# Canadian_Maid_v3.net
KiCad netlist of a schematic drawn in EAGLE
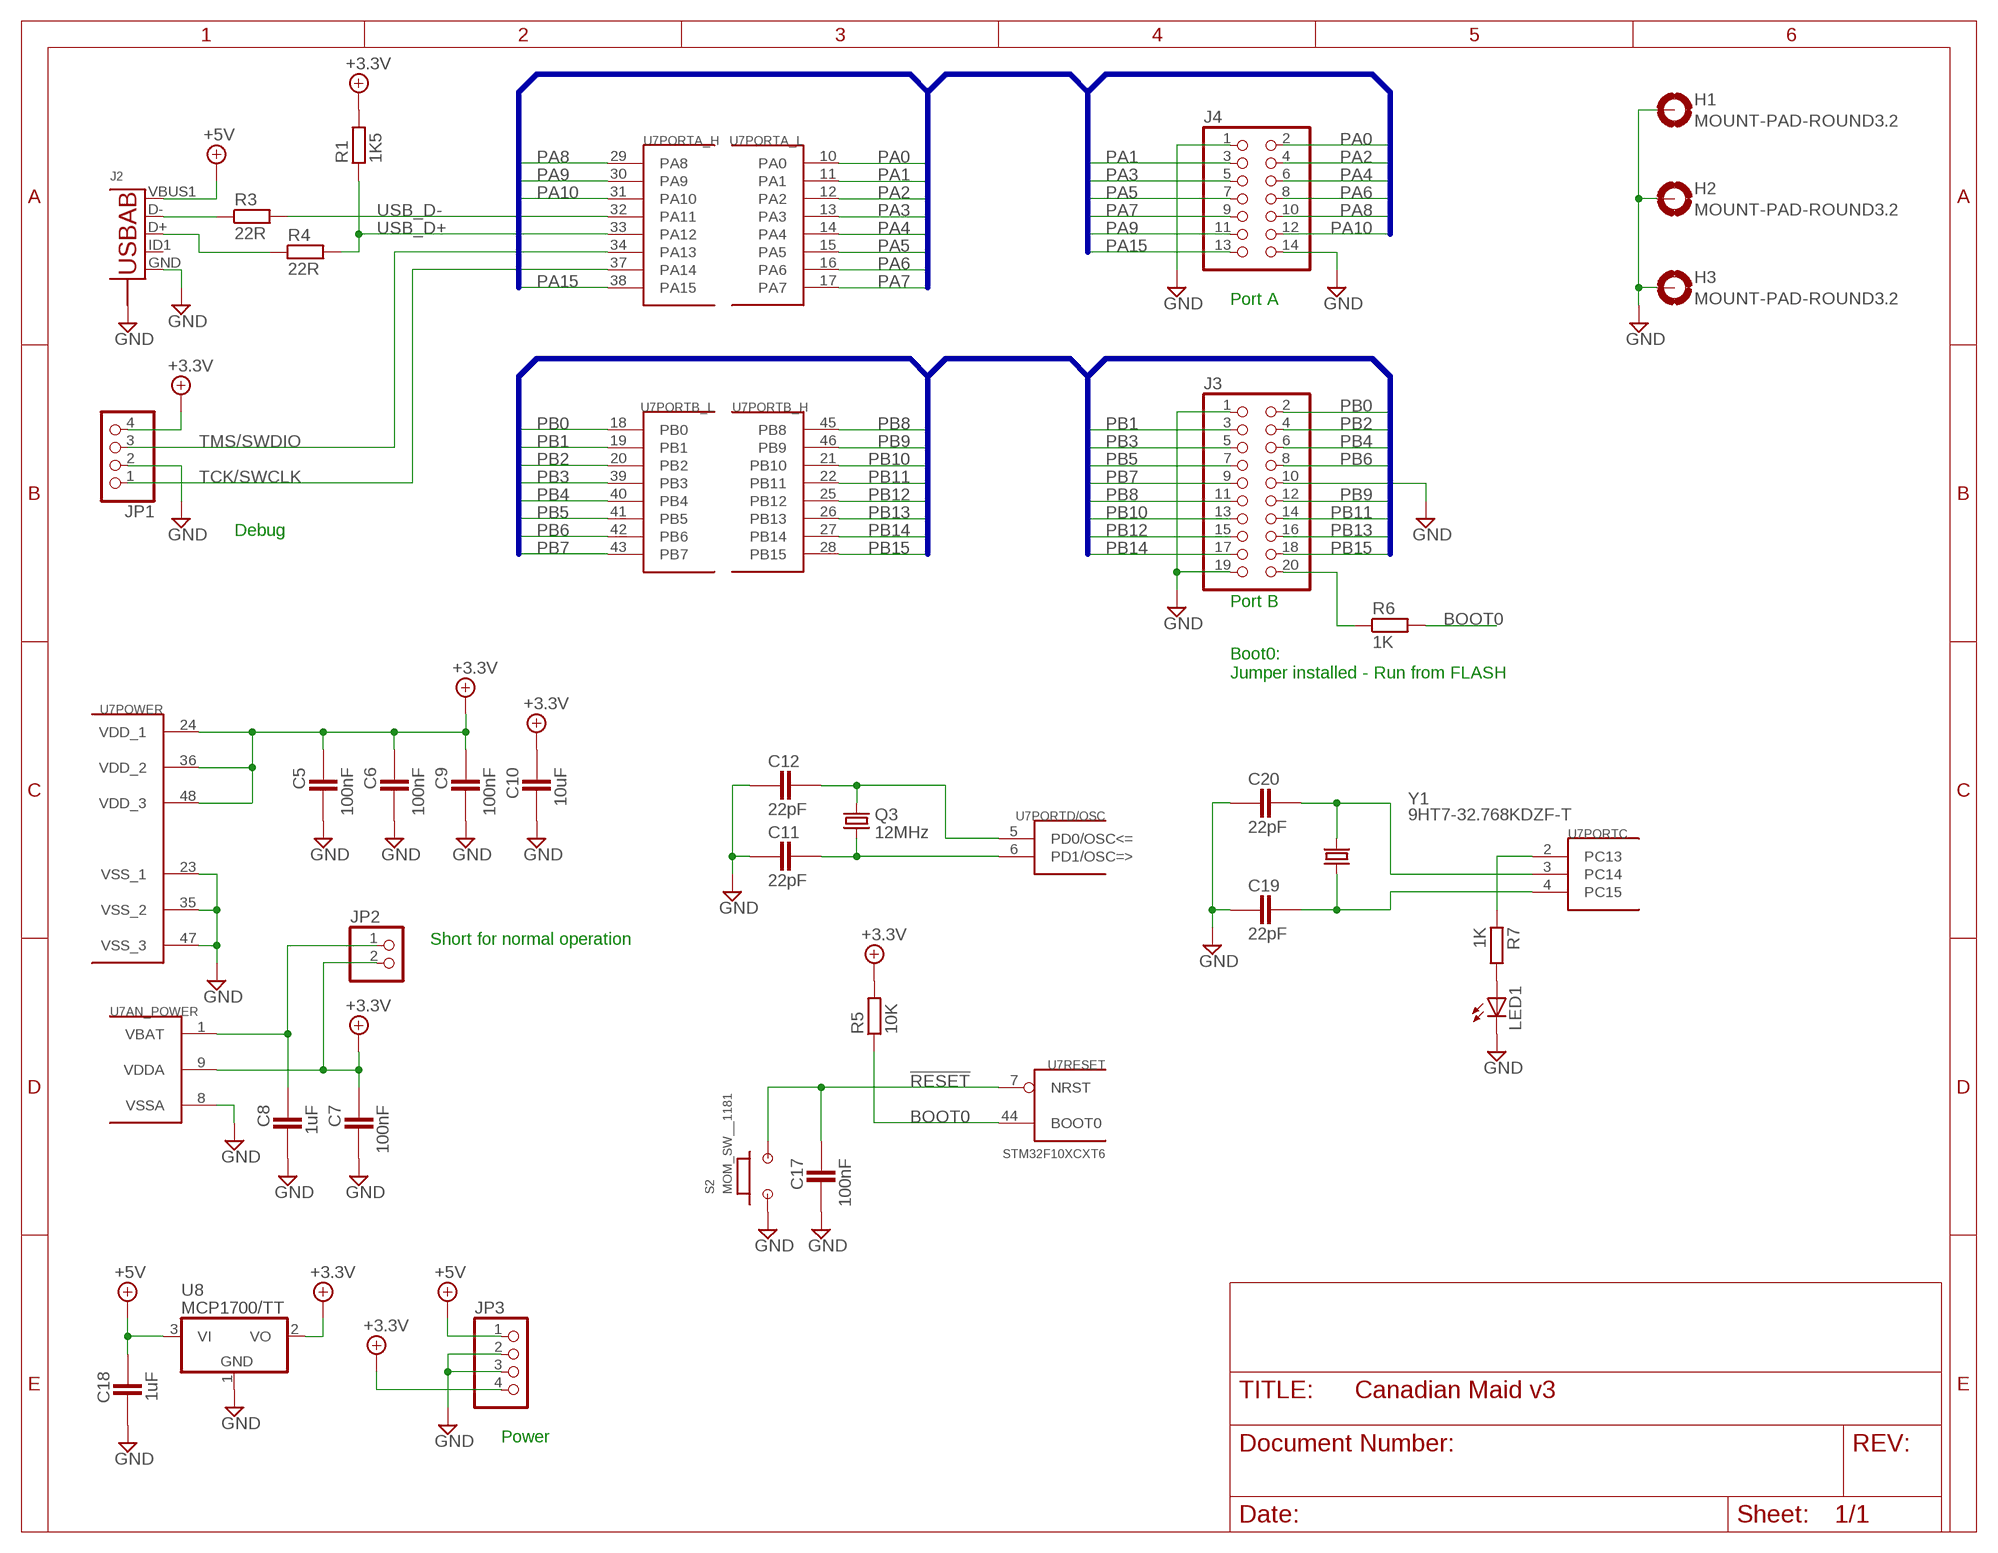
[diagram p0: schematic, sheet 1]

(export (version "E")
  (design (tool "Eeschema 10.0.6"))
  (components
    (comp (ref "C5")
      (value "100nF")
      (footprint "eagle-import:CAPC1005X60N")
      (libsource (lib "eagle-import") (part "CAPACITOR_0402"))
    )
    (comp (ref "C6")
      (value "100nF")
      (footprint "eagle-import:CAPC1005X60N")
      (libsource (lib "eagle-import") (part "CAPACITOR_0402"))
    )
    (comp (ref "C7")
      (value "100nF")
      (footprint "eagle-import:CAPC1005X60N")
      (libsource (lib "eagle-import") (part "CAPACITOR_0402"))
    )
    (comp (ref "C8")
      (value "1uF")
      (footprint "eagle-import:CAPC1005X60N")
      (libsource (lib "eagle-import") (part "CAPACITOR_0402"))
    )
    (comp (ref "C9")
      (value "100nF")
      (footprint "eagle-import:CAPC1005X60N")
      (libsource (lib "eagle-import") (part "CAPACITOR_0402"))
    )
    (comp (ref "C10")
      (value "10uF")
      (footprint "eagle-import:CAPC2012X145AN")
      (libsource (lib "eagle-import") (part "CAPACITOR_0805"))
    )
    (comp (ref "C11")
      (value "22pF")
      (footprint "eagle-import:CAPC1005X60N")
      (libsource (lib "eagle-import") (part "CAPACITOR_0402"))
    )
    (comp (ref "C12")
      (value "22pF")
      (footprint "eagle-import:CAPC1005X60N")
      (libsource (lib "eagle-import") (part "CAPACITOR_0402"))
    )
    (comp (ref "C17")
      (value "100nF")
      (footprint "eagle-import:CAPC1005X60N")
      (libsource (lib "eagle-import") (part "CAPACITOR_0402"))
    )
    (comp (ref "C18")
      (value "1uF")
      (footprint "eagle-import:CAPC1608X92N")
      (libsource (lib "eagle-import") (part "CAPACITOR_0603"))
    )
    (comp (ref "C19")
      (value "22pF")
      (footprint "eagle-import:CAPC1005X60N")
      (libsource (lib "eagle-import") (part "CAPACITOR_0402"))
    )
    (comp (ref "C20")
      (value "22pF")
      (footprint "eagle-import:CAPC1005X60N")
      (libsource (lib "eagle-import") (part "CAPACITOR_0402"))
    )
    (comp (ref "H1")
      (value "MOUNT-PAD-ROUND3.2")
      (footprint "eagle-import:3,2-PAD")
      (libsource (lib "eagle-import") (part "MOUNT-PAD-ROUND3.2"))
    )
    (comp (ref "H2")
      (value "MOUNT-PAD-ROUND3.2")
      (footprint "eagle-import:3,2-PAD")
      (libsource (lib "eagle-import") (part "MOUNT-PAD-ROUND3.2"))
    )
    (comp (ref "H3")
      (value "MOUNT-PAD-ROUND3.2")
      (footprint "eagle-import:3,2-PAD")
      (libsource (lib "eagle-import") (part "MOUNT-PAD-ROUND3.2"))
    )
    (comp (ref "J2")
      (value "USB-ABBG")
      (footprint "eagle-import:USB-AB-MICRO-SMD_V03_SF")
      (libsource (lib "eagle-import") (part "USB-ABBG"))
    )
    (comp (ref "J3")
      (value "PINHD-2X10_2.54")
      (footprint "eagle-import:2X10")
      (libsource (lib "eagle-import") (part "PINHD-2X10_2.54"))
    )
    (comp (ref "J4")
      (value "PINHD-2X7S")
      (footprint "eagle-import:2X07")
      (libsource (lib "eagle-import") (part "PINHD-2X7S"))
    )
    (comp (ref "JP1")
      (value "PINHD-1X4_2.54")
      (footprint "eagle-import:1X04")
      (libsource (lib "eagle-import") (part "PINHD-1X4_2.54"))
    )
    (comp (ref "JP2")
      (value "PINHD-1X2_2.00")
      (footprint "eagle-import:1X02M")
      (libsource (lib "eagle-import") (part "PINHD-1X2_2.00"))
    )
    (comp (ref "JP3")
      (value "PINHD-1X4_2.54")
      (footprint "eagle-import:1X04")
      (libsource (lib "eagle-import") (part "PINHD-1X4_2.54"))
    )
    (comp (ref "LED1")
      (value "LEDSML0603")
      (footprint "eagle-import:SML0603")
      (libsource (lib "eagle-import") (part "LEDSML0603"))
    )
    (comp (ref "Q3")
      (value "12MHz")
      (footprint "eagle-import:HC49U-V")
      (libsource (lib "eagle-import") (part "CRYSTALHC49U-V"))
    )
    (comp (ref "R1")
      (value "1K5")
      (footprint "eagle-import:RESC1005X40AN")
      (libsource (lib "eagle-import") (part "RESISTOR_0402"))
    )
    (comp (ref "R3")
      (value "22R")
      (footprint "eagle-import:RESC1005X40AN")
      (libsource (lib "eagle-import") (part "RESISTOR_0402"))
    )
    (comp (ref "R4")
      (value "22R")
      (footprint "eagle-import:RESC1005X40AN")
      (libsource (lib "eagle-import") (part "RESISTOR_0402"))
    )
    (comp (ref "R5")
      (value "10K")
      (footprint "eagle-import:RESC1005X40AN")
      (libsource (lib "eagle-import") (part "RESISTOR_0402"))
    )
    (comp (ref "R6")
      (value "1K")
      (footprint "eagle-import:RESC1005X40AN")
      (libsource (lib "eagle-import") (part "RESISTOR_0402"))
    )
    (comp (ref "R7")
      (value "1K")
      (footprint "eagle-import:RESC1005X40AN")
      (libsource (lib "eagle-import") (part "RESISTOR_0402"))
    )
    (comp (ref "S2")
      (value "MOM_SW__1181")
      (footprint "eagle-import:MOM-1181")
      (libsource (lib "eagle-import") (part "MOM_SW__1181"))
    )
    (comp (ref "U7")
      (value "STM32F10XCXT6")
      (footprint "eagle-import:TQFP48")
      (libsource (lib "eagle-import") (part "STM32F10XCXT6"))
    )
    (comp (ref "U8")
      (value "MCP1700/TT")
      (footprint "eagle-import:SOT95P280X135-3N")
      (libsource (lib "eagle-import") (part "MCP1700/TT"))
    )
    (comp (ref "Y1")
      (value "9HT7-32.768KDZF-T")
      (footprint "eagle-import:9HT7")
      (libsource (lib "eagle-import") (part "XTAL_9HT4"))
    )
  )
  (nets
    (net (code "1") (name "+3.3V") (class "Default")
      (node (ref "C10") (pin "1") (pinfunction "1_1") (pintype "passive"))
      (node (ref "C5") (pin "1") (pinfunction "1_1") (pintype "passive"))
      (node (ref "C6") (pin "1") (pinfunction "1_1") (pintype "passive"))
      (node (ref "C7") (pin "1") (pinfunction "1_1") (pintype "passive"))
      (node (ref "C9") (pin "1") (pinfunction "1_1") (pintype "passive"))
      (node (ref "JP1") (pin "4") (pinfunction "4_4") (pintype "passive"))
      (node (ref "JP2") (pin "2") (pinfunction "2_2") (pintype "passive"))
      (node (ref "JP3") (pin "4") (pinfunction "4_4") (pintype "passive"))
      (node (ref "R1") (pin "2") (pinfunction "2_2") (pintype "passive"))
      (node (ref "R5") (pin "2") (pinfunction "2_2") (pintype "passive"))
      (node (ref "U7") (pin "24") (pinfunction "VDD_1_24") (pintype "power_in"))
      (node (ref "U7") (pin "36") (pinfunction "VDD_2_36") (pintype "power_in"))
      (node (ref "U7") (pin "48") (pinfunction "VDD_3_48") (pintype "power_in"))
      (node (ref "U7") (pin "9") (pinfunction "VDDA_9") (pintype "power_in"))
      (node (ref "U8") (pin "2") (pinfunction "VO_2") (pintype "passive"))
    )
    (net (code "2") (name "+5V") (class "Default")
      (node (ref "C18") (pin "1") (pinfunction "1_1") (pintype "passive"))
      (node (ref "J2") (pin "VBUS1") (pinfunction "VBUS_VBUS1") (pintype "bidirectional"))
      (node (ref "JP3") (pin "1") (pinfunction "1_1") (pintype "passive"))
      (node (ref "U8") (pin "3") (pinfunction "VI_3") (pintype "input"))
    )
    (net (code "3") (name "/BOOT0") (class "Default")
      (node (ref "R5") (pin "1") (pinfunction "1_1") (pintype "passive"))
      (node (ref "R6") (pin "2") (pinfunction "2_2") (pintype "passive"))
      (node (ref "U7") (pin "44") (pinfunction "BOOT0_44") (pintype "input"))
    )
    (net (code "4") (name "/PA0") (class "Default")
      (node (ref "J4") (pin "2") (pinfunction "2_2") (pintype "passive"))
      (node (ref "U7") (pin "10") (pinfunction "PA0_10") (pintype "bidirectional"))
    )
    (net (code "5") (name "/PA1") (class "Default")
      (node (ref "J4") (pin "3") (pinfunction "3_3") (pintype "passive"))
      (node (ref "U7") (pin "11") (pinfunction "PA1_11") (pintype "bidirectional"))
    )
    (net (code "6") (name "/PA2") (class "Default")
      (node (ref "J4") (pin "4") (pinfunction "4_4") (pintype "passive"))
      (node (ref "U7") (pin "12") (pinfunction "PA2_12") (pintype "bidirectional"))
    )
    (net (code "7") (name "/PA3") (class "Default")
      (node (ref "J4") (pin "5") (pinfunction "5_5") (pintype "passive"))
      (node (ref "U7") (pin "13") (pinfunction "PA3_13") (pintype "bidirectional"))
    )
    (net (code "8") (name "/PA4") (class "Default")
      (node (ref "J4") (pin "6") (pinfunction "6_6") (pintype "passive"))
      (node (ref "U7") (pin "14") (pinfunction "PA4_14") (pintype "bidirectional"))
    )
    (net (code "9") (name "/PA5") (class "Default")
      (node (ref "J4") (pin "7") (pinfunction "7_7") (pintype "passive"))
      (node (ref "U7") (pin "15") (pinfunction "PA5_15") (pintype "bidirectional"))
    )
    (net (code "10") (name "/PA6") (class "Default")
      (node (ref "J4") (pin "8") (pinfunction "8_8") (pintype "passive"))
      (node (ref "U7") (pin "16") (pinfunction "PA6_16") (pintype "bidirectional"))
    )
    (net (code "11") (name "/PA7") (class "Default")
      (node (ref "J4") (pin "9") (pinfunction "9_9") (pintype "passive"))
      (node (ref "U7") (pin "17") (pinfunction "PA7_17") (pintype "bidirectional"))
    )
    (net (code "12") (name "/PA8") (class "Default")
      (node (ref "J4") (pin "10") (pinfunction "10_10") (pintype "passive"))
      (node (ref "U7") (pin "29") (pinfunction "PA8_29") (pintype "bidirectional"))
    )
    (net (code "13") (name "/PA9") (class "Default")
      (node (ref "J4") (pin "11") (pinfunction "11_11") (pintype "passive"))
      (node (ref "U7") (pin "30") (pinfunction "PA9_30") (pintype "bidirectional"))
    )
    (net (code "14") (name "/PA10") (class "Default")
      (node (ref "J4") (pin "12") (pinfunction "12_12") (pintype "passive"))
      (node (ref "U7") (pin "31") (pinfunction "PA10_31") (pintype "bidirectional"))
    )
    (net (code "15") (name "/PA15") (class "Default")
      (node (ref "J4") (pin "13") (pinfunction "13_13") (pintype "passive"))
      (node (ref "U7") (pin "38") (pinfunction "PA15_38") (pintype "bidirectional"))
    )
    (net (code "16") (name "/PB0") (class "Default")
      (node (ref "J3") (pin "2") (pinfunction "2_2") (pintype "passive"))
      (node (ref "U7") (pin "18") (pinfunction "PB0_18") (pintype "bidirectional"))
    )
    (net (code "17") (name "/PB1") (class "Default")
      (node (ref "J3") (pin "3") (pinfunction "3_3") (pintype "passive"))
      (node (ref "U7") (pin "19") (pinfunction "PB1_19") (pintype "bidirectional"))
    )
    (net (code "18") (name "/PB2") (class "Default")
      (node (ref "J3") (pin "4") (pinfunction "4_4") (pintype "passive"))
      (node (ref "U7") (pin "20") (pinfunction "PB2_20") (pintype "bidirectional"))
    )
    (net (code "19") (name "/PB3") (class "Default")
      (node (ref "J3") (pin "5") (pinfunction "5_5") (pintype "passive"))
      (node (ref "U7") (pin "39") (pinfunction "PB3_39") (pintype "bidirectional"))
    )
    (net (code "20") (name "/PB4") (class "Default")
      (node (ref "J3") (pin "6") (pinfunction "6_6") (pintype "passive"))
      (node (ref "U7") (pin "40") (pinfunction "PB4_40") (pintype "bidirectional"))
    )
    (net (code "21") (name "/PB5") (class "Default")
      (node (ref "J3") (pin "7") (pinfunction "7_7") (pintype "passive"))
      (node (ref "U7") (pin "41") (pinfunction "PB5_41") (pintype "bidirectional"))
    )
    (net (code "22") (name "/PB6") (class "Default")
      (node (ref "J3") (pin "8") (pinfunction "8_8") (pintype "passive"))
      (node (ref "U7") (pin "42") (pinfunction "PB6_42") (pintype "bidirectional"))
    )
    (net (code "23") (name "/PB7") (class "Default")
      (node (ref "J3") (pin "9") (pinfunction "9_9") (pintype "passive"))
      (node (ref "U7") (pin "43") (pinfunction "PB7_43") (pintype "bidirectional"))
    )
    (net (code "24") (name "/PB8") (class "Default")
      (node (ref "J3") (pin "11") (pinfunction "11_11") (pintype "passive"))
      (node (ref "U7") (pin "45") (pinfunction "PB8_45") (pintype "bidirectional"))
    )
    (net (code "25") (name "/PB9") (class "Default")
      (node (ref "J3") (pin "12") (pinfunction "12_12") (pintype "passive"))
      (node (ref "U7") (pin "46") (pinfunction "PB9_46") (pintype "bidirectional"))
    )
    (net (code "26") (name "/PB10") (class "Default")
      (node (ref "J3") (pin "13") (pinfunction "13_13") (pintype "passive"))
      (node (ref "U7") (pin "21") (pinfunction "PB10_21") (pintype "bidirectional"))
    )
    (net (code "27") (name "/PB11") (class "Default")
      (node (ref "J3") (pin "14") (pinfunction "14_14") (pintype "passive"))
      (node (ref "U7") (pin "22") (pinfunction "PB11_22") (pintype "bidirectional"))
    )
    (net (code "28") (name "/PB12") (class "Default")
      (node (ref "J3") (pin "15") (pinfunction "15_15") (pintype "passive"))
      (node (ref "U7") (pin "25") (pinfunction "PB12_25") (pintype "bidirectional"))
    )
    (net (code "29") (name "/PB13") (class "Default")
      (node (ref "J3") (pin "16") (pinfunction "16_16") (pintype "passive"))
      (node (ref "U7") (pin "26") (pinfunction "PB13_26") (pintype "bidirectional"))
    )
    (net (code "30") (name "/PB14") (class "Default")
      (node (ref "J3") (pin "17") (pinfunction "17_17") (pintype "passive"))
      (node (ref "U7") (pin "27") (pinfunction "PB14_27") (pintype "bidirectional"))
    )
    (net (code "31") (name "/PB15") (class "Default")
      (node (ref "J3") (pin "18") (pinfunction "18_18") (pintype "passive"))
      (node (ref "U7") (pin "28") (pinfunction "PB15_28") (pintype "bidirectional"))
    )
    (net (code "32") (name "/TCK{slash}SWCLK") (class "Default")
      (node (ref "JP1") (pin "1") (pinfunction "1_1") (pintype "passive"))
      (node (ref "U7") (pin "37") (pinfunction "PA14_37") (pintype "bidirectional"))
    )
    (net (code "33") (name "/TMS{slash}SWDIO") (class "Default")
      (node (ref "JP1") (pin "3") (pinfunction "3_3") (pintype "passive"))
      (node (ref "U7") (pin "34") (pinfunction "PA13_34") (pintype "bidirectional"))
    )
    (net (code "34") (name "/USB_D+") (class "Default")
      (node (ref "R1") (pin "1") (pinfunction "1_1") (pintype "passive"))
      (node (ref "R4") (pin "2") (pinfunction "2_2") (pintype "passive"))
      (node (ref "U7") (pin "33") (pinfunction "PA12_33") (pintype "bidirectional"))
    )
    (net (code "35") (name "/USB_D-") (class "Default")
      (node (ref "R3") (pin "2") (pinfunction "2_2") (pintype "passive"))
      (node (ref "U7") (pin "32") (pinfunction "PA11_32") (pintype "bidirectional"))
    )
    (net (code "36") (name "/~{RESET}") (class "Default")
      (node (ref "C17") (pin "1") (pinfunction "1_1") (pintype "passive"))
      (node (ref "S2") (pin "2") (pinfunction "2_2") (pintype "bidirectional"))
      (node (ref "U7") (pin "7") (pinfunction "NRST_7") (pintype "input"))
    )
    (net (code "37") (name "GND") (class "Default")
      (node (ref "C10") (pin "2") (pinfunction "2_2") (pintype "passive"))
      (node (ref "C11") (pin "1") (pinfunction "1_1") (pintype "passive"))
      (node (ref "C12") (pin "1") (pinfunction "1_1") (pintype "passive"))
      (node (ref "C17") (pin "2") (pinfunction "2_2") (pintype "passive"))
      (node (ref "C18") (pin "2") (pinfunction "2_2") (pintype "passive"))
      (node (ref "C19") (pin "1") (pinfunction "1_1") (pintype "passive"))
      (node (ref "C20") (pin "1") (pinfunction "1_1") (pintype "passive"))
      (node (ref "C5") (pin "2") (pinfunction "2_2") (pintype "passive"))
      (node (ref "C6") (pin "2") (pinfunction "2_2") (pintype "passive"))
      (node (ref "C7") (pin "2") (pinfunction "2_2") (pintype "passive"))
      (node (ref "C8") (pin "2") (pinfunction "2_2") (pintype "passive"))
      (node (ref "C9") (pin "2") (pinfunction "2_2") (pintype "passive"))
      (node (ref "H1") (pin "B3,2") (pinfunction "MOUNT_B3,2") (pintype "passive"))
      (node (ref "H2") (pin "B3,2") (pinfunction "MOUNT_B3,2") (pintype "passive"))
      (node (ref "H3") (pin "B3,2") (pinfunction "MOUNT_B3,2") (pintype "passive"))
      (node (ref "J2") (pin "GND") (pinfunction "GND_GND") (pintype "bidirectional"))
      (node (ref "J2") (pin "S1") (pinfunction "S_S1") (pintype "bidirectional"))
      (node (ref "J2") (pin "S2") (pinfunction "S_S2") (pintype "bidirectional"))
      (node (ref "J2") (pin "S3") (pinfunction "S_S3") (pintype "bidirectional"))
      (node (ref "J2") (pin "S4") (pinfunction "S_S4") (pintype "bidirectional"))
      (node (ref "J3") (pin "1") (pinfunction "1_1") (pintype "passive"))
      (node (ref "J3") (pin "10") (pinfunction "10_10") (pintype "passive"))
      (node (ref "J3") (pin "19") (pinfunction "19_19") (pintype "passive"))
      (node (ref "J4") (pin "1") (pinfunction "1_1") (pintype "passive"))
      (node (ref "J4") (pin "14") (pinfunction "14_14") (pintype "passive"))
      (node (ref "JP1") (pin "2") (pinfunction "2_2") (pintype "passive"))
      (node (ref "JP3") (pin "2") (pinfunction "2_2") (pintype "passive"))
      (node (ref "JP3") (pin "3") (pinfunction "3_3") (pintype "passive"))
      (node (ref "LED1") (pin "C") (pinfunction "C_C") (pintype "passive"))
      (node (ref "S2") (pin "1") (pinfunction "1_1") (pintype "bidirectional"))
      (node (ref "U7") (pin "23") (pinfunction "VSS_1_23") (pintype "power_in"))
      (node (ref "U7") (pin "35") (pinfunction "VSS_2_35") (pintype "power_in"))
      (node (ref "U7") (pin "47") (pinfunction "VSS_3_47") (pintype "power_in"))
      (node (ref "U7") (pin "8") (pinfunction "VSSA_8") (pintype "power_in"))
      (node (ref "U8") (pin "1") (pinfunction "GND_1") (pintype "passive"))
    )
    (net (code "38") (name "Net-(J2-PadD+)") (class "Default")
      (node (ref "J2") (pin "D+") (pinfunction "D+_D+") (pintype "bidirectional"))
      (node (ref "R4") (pin "1") (pinfunction "1_1") (pintype "passive"))
    )
    (net (code "39") (name "Net-(J2-PadD-)") (class "Default")
      (node (ref "J2") (pin "D-") (pinfunction "D-_D-") (pintype "bidirectional"))
      (node (ref "R3") (pin "1") (pinfunction "1_1") (pintype "passive"))
    )
    (net (code "40") (name "Net-(J3-Pad20)") (class "Default")
      (node (ref "J3") (pin "20") (pinfunction "20_20") (pintype "passive"))
      (node (ref "R6") (pin "1") (pinfunction "1_1") (pintype "passive"))
    )
    (net (code "41") (name "Net-(LED1-PadA)") (class "Default")
      (node (ref "LED1") (pin "A") (pinfunction "A_A") (pintype "passive"))
      (node (ref "R7") (pin "2") (pinfunction "2_2") (pintype "passive"))
    )
    (net (code "42") (name "Net-(U7A-VBAT)") (class "Default")
      (node (ref "C8") (pin "1") (pinfunction "1_1") (pintype "passive"))
      (node (ref "JP2") (pin "1") (pinfunction "1_1") (pintype "passive"))
      (node (ref "U7") (pin "1") (pinfunction "VBAT_1") (pintype "power_in"))
    )
    (net (code "43") (name "Net-(U7F-PC13)") (class "Default")
      (node (ref "R7") (pin "1") (pinfunction "1_1") (pintype "passive"))
      (node (ref "U7") (pin "2") (pinfunction "PC13_2") (pintype "bidirectional"))
    )
    (net (code "44") (name "Net-(U7F-PC14)") (class "Default")
      (node (ref "C20") (pin "2") (pinfunction "2_2") (pintype "passive"))
      (node (ref "U7") (pin "3") (pinfunction "PC14_3") (pintype "bidirectional"))
      (node (ref "Y1") (pin "4") (pinfunction "2_4") (pintype "passive"))
    )
    (net (code "45") (name "Net-(U7F-PC15)") (class "Default")
      (node (ref "C19") (pin "2") (pinfunction "2_2") (pintype "passive"))
      (node (ref "U7") (pin "4") (pinfunction "PC15_4") (pintype "bidirectional"))
      (node (ref "Y1") (pin "1") (pinfunction "1_1") (pintype "passive"))
    )
    (net (code "46") (name "Net-(U7G-PD0{slash}OSC<=)") (class "Default")
      (node (ref "C12") (pin "2") (pinfunction "2_2") (pintype "passive"))
      (node (ref "Q3") (pin "2") (pinfunction "2_2") (pintype "passive"))
      (node (ref "U7") (pin "5") (pinfunction "PD0/OSC<=_5") (pintype "bidirectional"))
    )
    (net (code "47") (name "Net-(U7G-PD1{slash}OSC=>)") (class "Default")
      (node (ref "C11") (pin "2") (pinfunction "2_2") (pintype "passive"))
      (node (ref "Q3") (pin "1") (pinfunction "1_1") (pintype "passive"))
      (node (ref "U7") (pin "6") (pinfunction "PD1/OSC=>_6") (pintype "bidirectional"))
    )
    (net (code "48") (name "unconnected-(J2-USBID-PadID1)") (class "Default")
      (node (ref "J2") (pin "ID1") (pinfunction "USBID_ID1") (pintype "bidirectional"))
    )
  )
)
